# Pi_Board.net
KiCad netlist of a schematic drawn in EAGLE
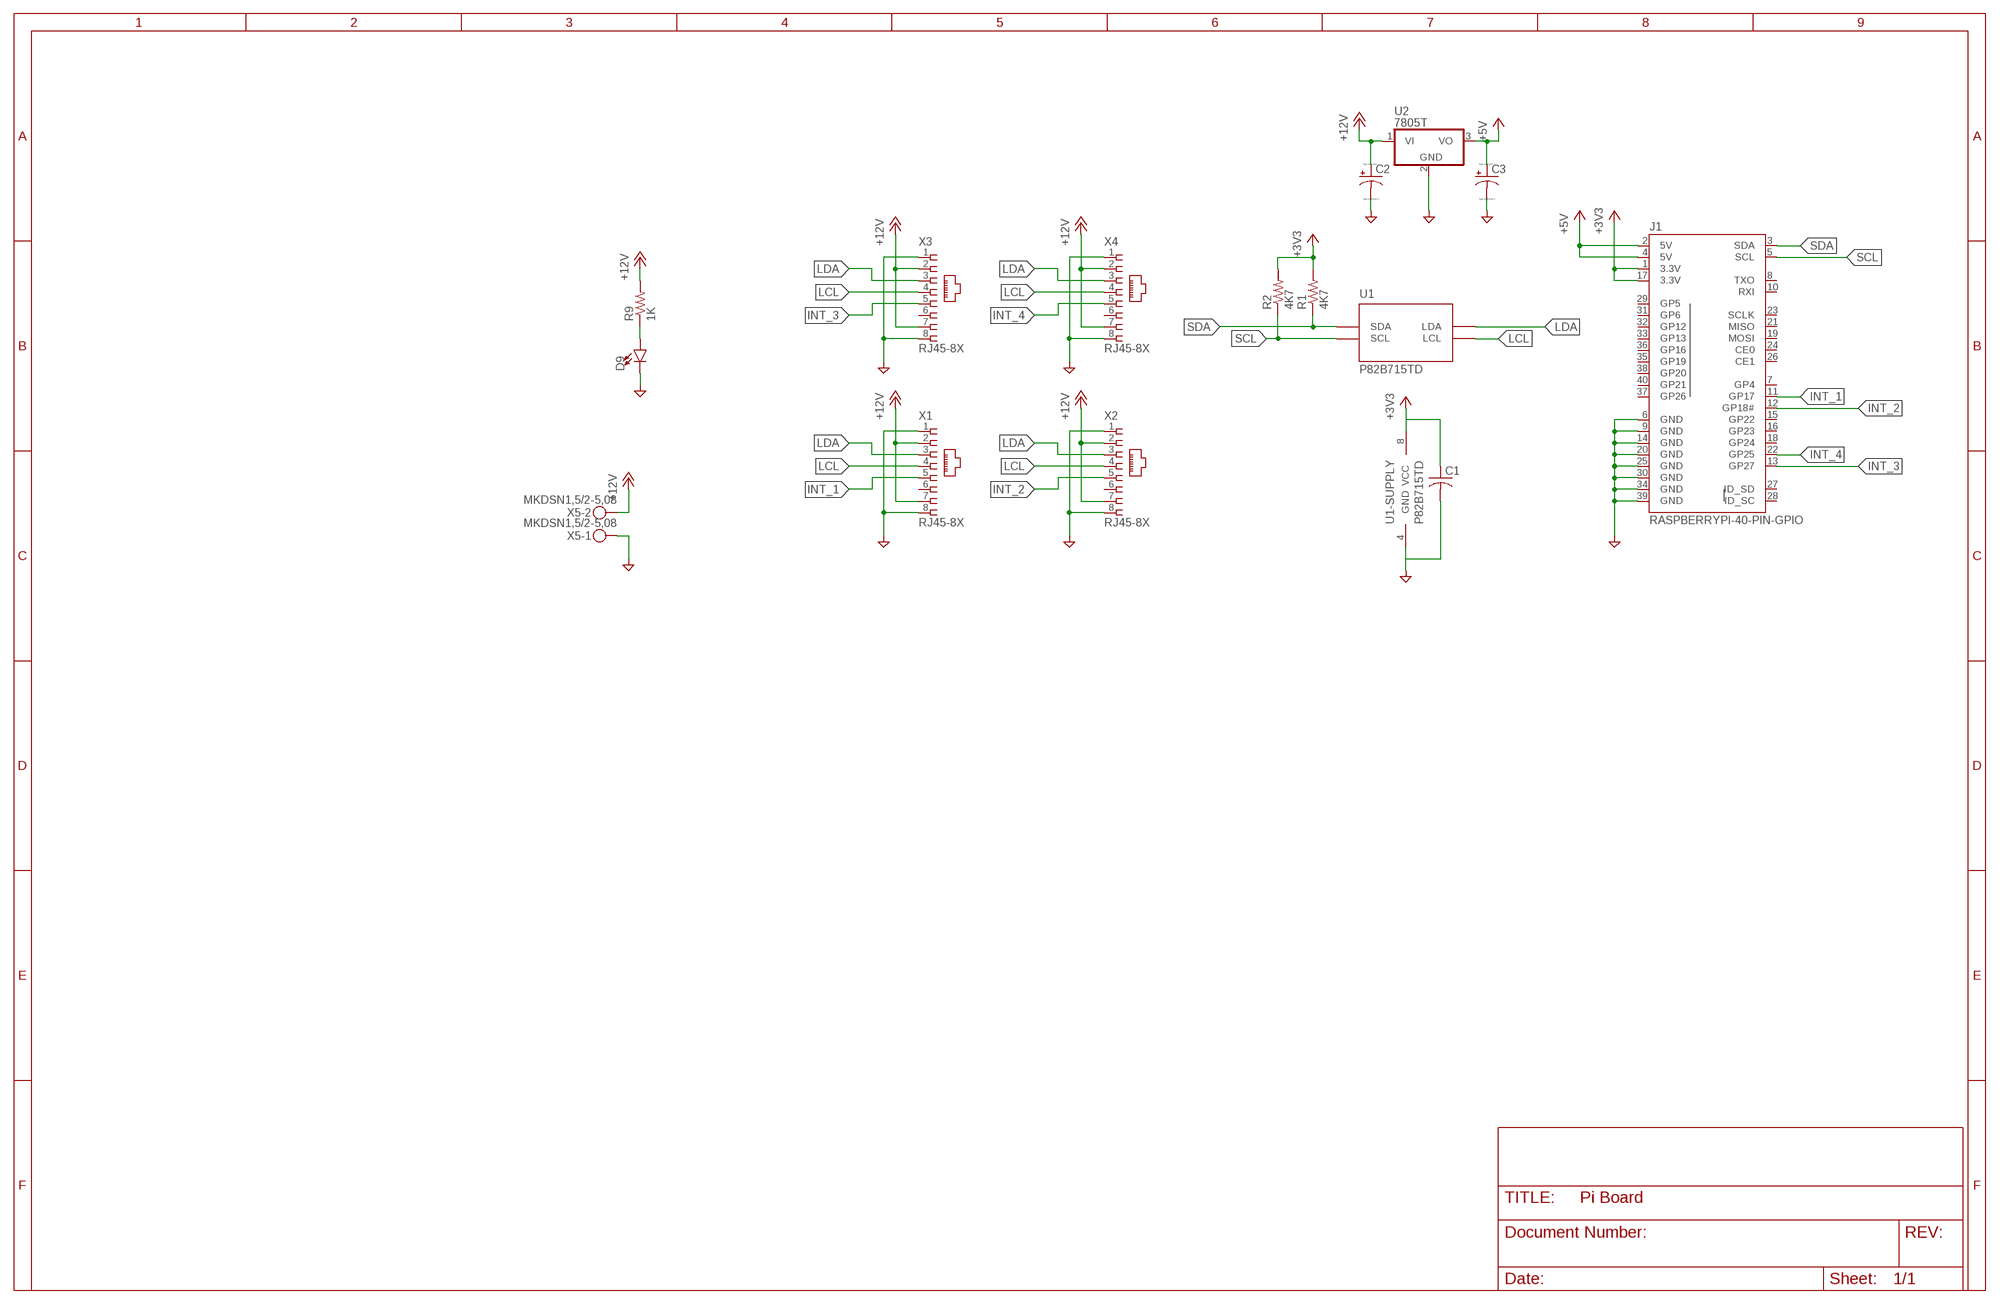
[diagram p0: schematic, sheet 1]

(export (version "E")
  (design (tool "Eeschema 10.0.6"))
  (components
    (comp (ref "C1")
      (value "C-USC0805")
      (footprint "eagle-import:C0805")
      (libsource (lib "eagle-import") (part "C-USC0805"))
    )
    (comp (ref "C2")
      (value "CPOL-USC")
      (footprint "eagle-import:PANASONIC_C")
      (libsource (lib "eagle-import") (part "CPOL-USC"))
    )
    (comp (ref "C3")
      (value "CPOL-USC")
      (footprint "eagle-import:PANASONIC_C")
      (libsource (lib "eagle-import") (part "CPOL-USC"))
    )
    (comp (ref "D9")
      (value "LED3MM")
      (footprint "eagle-import:LED_3MM")
      (libsource (lib "eagle-import") (part "LED3MM"))
    )
    (comp (ref "J1")
      (value "RASPBERRYPI-40-PIN-GPIO")
      (footprint "eagle-import:2X20-SHROUDED")
      (libsource (lib "eagle-import") (part "RASPBERRYPI-40-PIN-GPIO"))
    )
    (comp (ref "R1")
      (value "4K7")
      (footprint "eagle-import:R0805")
      (libsource (lib "eagle-import") (part "R-US_R0805"))
    )
    (comp (ref "R2")
      (value "4K7")
      (footprint "eagle-import:R0805")
      (libsource (lib "eagle-import") (part "R-US_R0805"))
    )
    (comp (ref "R9")
      (value "1K")
      (footprint "eagle-import:R0805")
      (libsource (lib "eagle-import") (part "R-US_R0805"))
    )
    (comp (ref "U1")
      (value "P82B715TD")
      (footprint "eagle-import:SOIC-8")
      (fields (field (name "MANUFACTURER") "NXP Semiconductors") (field (name "PART_NUMBER") "P82B715TD,118"))
      (libsource (lib "eagle-import") (part "P82B715?TD"))
    )
    (comp (ref "U2")
      (value "7805T")
      (footprint "eagle-import:TO220H")
      (libsource (lib "eagle-import") (part "78T05"))
    )
    (comp (ref "X1")
      (value "RJ45-8X")
      (footprint "eagle-import:RJ45-NO-SHIELD")
      (libsource (lib "eagle-import") (part "RJ45-8X"))
    )
    (comp (ref "X2")
      (value "RJ45-8X")
      (footprint "eagle-import:RJ45-NO-SHIELD")
      (libsource (lib "eagle-import") (part "RJ45-8X"))
    )
    (comp (ref "X3")
      (value "RJ45-8X")
      (footprint "eagle-import:RJ45-NO-SHIELD")
      (libsource (lib "eagle-import") (part "RJ45-8X"))
    )
    (comp (ref "X4")
      (value "RJ45-8X")
      (footprint "eagle-import:RJ45-NO-SHIELD")
      (libsource (lib "eagle-import") (part "RJ45-8X"))
    )
    (comp (ref "X5")
      (value "MKDSN1,5/2-5,08")
      (footprint "eagle-import:MKDSN1,5_2-5,08")
      (libsource (lib "eagle-import") (part "MKDSN1,5/2-5,08"))
    )
  )
  (nets
    (net (code "1") (name "+3V3") (class "Default")
      (node (ref "C1") (pin "1") (pinfunction "1_1") (pintype "passive"))
      (node (ref "J1") (pin "1") (pinfunction "3.3V_1") (pintype "power_in"))
      (node (ref "J1") (pin "17") (pinfunction "3.3V_17") (pintype "power_in"))
      (node (ref "R1") (pin "2") (pinfunction "2_2") (pintype "passive"))
      (node (ref "R2") (pin "2") (pinfunction "2_2") (pintype "passive"))
      (node (ref "U1") (pin "8") (pinfunction "VCC_8") (pintype "bidirectional"))
    )
    (net (code "2") (name "+5V") (class "Default")
      (node (ref "C3") (pin "+") (pinfunction "+_+") (pintype "passive"))
      (node (ref "J1") (pin "2") (pinfunction "5V_2") (pintype "power_in"))
      (node (ref "J1") (pin "4") (pinfunction "5V_4") (pintype "power_in"))
      (node (ref "U2") (pin "3") (pinfunction "VO_3") (pintype "passive"))
    )
    (net (code "3") (name "+12V") (class "Default")
      (node (ref "C2") (pin "+") (pinfunction "+_+") (pintype "passive"))
      (node (ref "R9") (pin "2") (pinfunction "2_2") (pintype "passive"))
      (node (ref "U2") (pin "1") (pinfunction "VI_1") (pintype "input"))
      (node (ref "X1") (pin "2") (pinfunction "2_2") (pintype "passive"))
      (node (ref "X1") (pin "7") (pinfunction "7_7") (pintype "passive"))
      (node (ref "X2") (pin "2") (pinfunction "2_2") (pintype "passive"))
      (node (ref "X2") (pin "7") (pinfunction "7_7") (pintype "passive"))
      (node (ref "X3") (pin "2") (pinfunction "2_2") (pintype "passive"))
      (node (ref "X3") (pin "7") (pinfunction "7_7") (pintype "passive"))
      (node (ref "X4") (pin "2") (pinfunction "2_2") (pintype "passive"))
      (node (ref "X4") (pin "7") (pinfunction "7_7") (pintype "passive"))
      (node (ref "X5") (pin "2") (pinfunction "KL_2") (pintype "passive"))
    )
    (net (code "4") (name "INT_1") (class "Default")
      (node (ref "J1") (pin "11") (pinfunction "GP17_11") (pintype "bidirectional"))
      (node (ref "X1") (pin "5") (pinfunction "5_5") (pintype "passive"))
    )
    (net (code "5") (name "INT_2") (class "Default")
      (node (ref "J1") (pin "12") (pinfunction "GP18#_12") (pintype "bidirectional"))
      (node (ref "X2") (pin "5") (pinfunction "5_5") (pintype "passive"))
    )
    (net (code "6") (name "INT_3") (class "Default")
      (node (ref "J1") (pin "13") (pinfunction "GP27_13") (pintype "bidirectional"))
      (node (ref "X3") (pin "5") (pinfunction "5_5") (pintype "passive"))
    )
    (net (code "7") (name "INT_4") (class "Default")
      (node (ref "J1") (pin "22") (pinfunction "GP25_22") (pintype "bidirectional"))
      (node (ref "X4") (pin "5") (pinfunction "5_5") (pintype "passive"))
    )
    (net (code "8") (name "LCL") (class "Default")
      (node (ref "U1") (pin "2") (pinfunction "LCL_2") (pintype "bidirectional"))
      (node (ref "X1") (pin "4") (pinfunction "4_4") (pintype "passive"))
      (node (ref "X2") (pin "4") (pinfunction "4_4") (pintype "passive"))
      (node (ref "X3") (pin "4") (pinfunction "4_4") (pintype "passive"))
      (node (ref "X4") (pin "4") (pinfunction "4_4") (pintype "passive"))
    )
    (net (code "9") (name "LDA") (class "Default")
      (node (ref "U1") (pin "7") (pinfunction "LDA_7") (pintype "bidirectional"))
      (node (ref "X1") (pin "3") (pinfunction "3_3") (pintype "passive"))
      (node (ref "X2") (pin "3") (pinfunction "3_3") (pintype "passive"))
      (node (ref "X3") (pin "3") (pinfunction "3_3") (pintype "passive"))
      (node (ref "X4") (pin "3") (pinfunction "3_3") (pintype "passive"))
    )
    (net (code "10") (name "Net-(D9-PadA)") (class "Default")
      (node (ref "D9") (pin "A") (pinfunction "A_A") (pintype "passive"))
      (node (ref "R9") (pin "1") (pinfunction "1_1") (pintype "passive"))
    )
    (net (code "11") (name "SCL") (class "Default")
      (node (ref "J1") (pin "5") (pinfunction "SCL_5") (pintype "bidirectional"))
      (node (ref "R2") (pin "1") (pinfunction "1_1") (pintype "passive"))
      (node (ref "U1") (pin "3") (pinfunction "SCL_3") (pintype "bidirectional"))
    )
    (net (code "12") (name "SDA") (class "Default")
      (node (ref "J1") (pin "3") (pinfunction "SDA_3") (pintype "bidirectional"))
      (node (ref "R1") (pin "1") (pinfunction "1_1") (pintype "passive"))
      (node (ref "U1") (pin "6") (pinfunction "SDA_6") (pintype "bidirectional"))
    )
    (net (code "13") (name "VDG") (class "Default")
      (node (ref "C1") (pin "2") (pinfunction "2_2") (pintype "passive"))
      (node (ref "C2") (pin "-") (pinfunction "-_-") (pintype "passive"))
      (node (ref "C3") (pin "-") (pinfunction "-_-") (pintype "passive"))
      (node (ref "D9") (pin "K") (pinfunction "C_K") (pintype "passive"))
      (node (ref "J1") (pin "14") (pinfunction "GND_14") (pintype "power_in"))
      (node (ref "J1") (pin "20") (pinfunction "GND_20") (pintype "power_in"))
      (node (ref "J1") (pin "25") (pinfunction "GND_25") (pintype "power_in"))
      (node (ref "J1") (pin "30") (pinfunction "GND_30") (pintype "power_in"))
      (node (ref "J1") (pin "34") (pinfunction "GND_34") (pintype "power_in"))
      (node (ref "J1") (pin "39") (pinfunction "GND_39") (pintype "power_in"))
      (node (ref "J1") (pin "6") (pinfunction "GND_6") (pintype "power_in"))
      (node (ref "J1") (pin "9") (pinfunction "GND_9") (pintype "power_in"))
      (node (ref "U1") (pin "4") (pinfunction "GND_4") (pintype "bidirectional"))
      (node (ref "U2") (pin "2") (pinfunction "GND_2") (pintype "passive"))
      (node (ref "X1") (pin "1") (pinfunction "1_1") (pintype "passive"))
      (node (ref "X1") (pin "8") (pinfunction "8_8") (pintype "passive"))
      (node (ref "X2") (pin "1") (pinfunction "1_1") (pintype "passive"))
      (node (ref "X2") (pin "8") (pinfunction "8_8") (pintype "passive"))
      (node (ref "X3") (pin "1") (pinfunction "1_1") (pintype "passive"))
      (node (ref "X3") (pin "8") (pinfunction "8_8") (pintype "passive"))
      (node (ref "X4") (pin "1") (pinfunction "1_1") (pintype "passive"))
      (node (ref "X4") (pin "8") (pinfunction "8_8") (pintype "passive"))
      (node (ref "X5") (pin "1") (pinfunction "KL_1") (pintype "passive"))
    )
    (net (code "14") (name "unconnected-(J1-CE0-Pad24)") (class "Default")
      (node (ref "J1") (pin "24") (pinfunction "CE0_24") (pintype "output"))
    )
    (net (code "15") (name "unconnected-(J1-CE1-Pad26)") (class "Default")
      (node (ref "J1") (pin "26") (pinfunction "CE1_26") (pintype "output"))
    )
    (net (code "16") (name "unconnected-(J1-GP4-Pad7)") (class "Default")
      (node (ref "J1") (pin "7") (pinfunction "GP4_7") (pintype "bidirectional"))
    )
    (net (code "17") (name "unconnected-(J1-GP5-Pad29)") (class "Default")
      (node (ref "J1") (pin "29") (pinfunction "GP5_29") (pintype "bidirectional"))
    )
    (net (code "18") (name "unconnected-(J1-GP6-Pad31)") (class "Default")
      (node (ref "J1") (pin "31") (pinfunction "GP6_31") (pintype "bidirectional"))
    )
    (net (code "19") (name "unconnected-(J1-GP12-Pad32)") (class "Default")
      (node (ref "J1") (pin "32") (pinfunction "GP12_32") (pintype "bidirectional"))
    )
    (net (code "20") (name "unconnected-(J1-GP13-Pad33)") (class "Default")
      (node (ref "J1") (pin "33") (pinfunction "GP13_33") (pintype "bidirectional"))
    )
    (net (code "21") (name "unconnected-(J1-GP16-Pad36)") (class "Default")
      (node (ref "J1") (pin "36") (pinfunction "GP16_36") (pintype "bidirectional"))
    )
    (net (code "22") (name "unconnected-(J1-GP19-Pad35)") (class "Default")
      (node (ref "J1") (pin "35") (pinfunction "GP19_35") (pintype "bidirectional"))
    )
    (net (code "23") (name "unconnected-(J1-GP20-Pad38)") (class "Default")
      (node (ref "J1") (pin "38") (pinfunction "GP20_38") (pintype "bidirectional"))
    )
    (net (code "24") (name "unconnected-(J1-GP21-Pad40)") (class "Default")
      (node (ref "J1") (pin "40") (pinfunction "GP21_40") (pintype "bidirectional"))
    )
    (net (code "25") (name "unconnected-(J1-GP22-Pad15)") (class "Default")
      (node (ref "J1") (pin "15") (pinfunction "GP22_15") (pintype "bidirectional"))
    )
    (net (code "26") (name "unconnected-(J1-GP23-Pad16)") (class "Default")
      (node (ref "J1") (pin "16") (pinfunction "GP23_16") (pintype "bidirectional"))
    )
    (net (code "27") (name "unconnected-(J1-GP24-Pad18)") (class "Default")
      (node (ref "J1") (pin "18") (pinfunction "GP24_18") (pintype "bidirectional"))
    )
    (net (code "28") (name "unconnected-(J1-GP26-Pad37)") (class "Default")
      (node (ref "J1") (pin "37") (pinfunction "GP26_37") (pintype "bidirectional"))
    )
    (net (code "29") (name "unconnected-(J1-ID_SC-Pad28)") (class "Default")
      (node (ref "J1") (pin "28") (pinfunction "ID_SC_28") (pintype "bidirectional"))
    )
    (net (code "30") (name "unconnected-(J1-ID_SD-Pad27)") (class "Default")
      (node (ref "J1") (pin "27") (pinfunction "ID_SD_27") (pintype "bidirectional"))
    )
    (net (code "31") (name "unconnected-(J1-MISO-Pad21)") (class "Default")
      (node (ref "J1") (pin "21") (pinfunction "MISO_21") (pintype "input"))
    )
    (net (code "32") (name "unconnected-(J1-MOSI-Pad19)") (class "Default")
      (node (ref "J1") (pin "19") (pinfunction "MOSI_19") (pintype "output"))
    )
    (net (code "33") (name "unconnected-(J1-RXI-Pad10)") (class "Default")
      (node (ref "J1") (pin "10") (pinfunction "RXI_10") (pintype "input"))
    )
    (net (code "34") (name "unconnected-(J1-SCLK-Pad23)") (class "Default")
      (node (ref "J1") (pin "23") (pinfunction "SCLK_23") (pintype "output"))
    )
    (net (code "35") (name "unconnected-(J1-TXO-Pad8)") (class "Default")
      (node (ref "J1") (pin "8") (pinfunction "TXO_8") (pintype "output"))
    )
    (net (code "36") (name "unconnected-(X1-Pad6)") (class "Default")
      (node (ref "X1") (pin "6") (pinfunction "6_6") (pintype "passive"))
    )
    (net (code "37") (name "unconnected-(X2-Pad6)") (class "Default")
      (node (ref "X2") (pin "6") (pinfunction "6_6") (pintype "passive"))
    )
    (net (code "38") (name "unconnected-(X3-Pad6)") (class "Default")
      (node (ref "X3") (pin "6") (pinfunction "6_6") (pintype "passive"))
    )
    (net (code "39") (name "unconnected-(X4-Pad6)") (class "Default")
      (node (ref "X4") (pin "6") (pinfunction "6_6") (pintype "passive"))
    )
  )
)
